# Power.net
KiCad netlist of a schematic drawn in Altium Designer
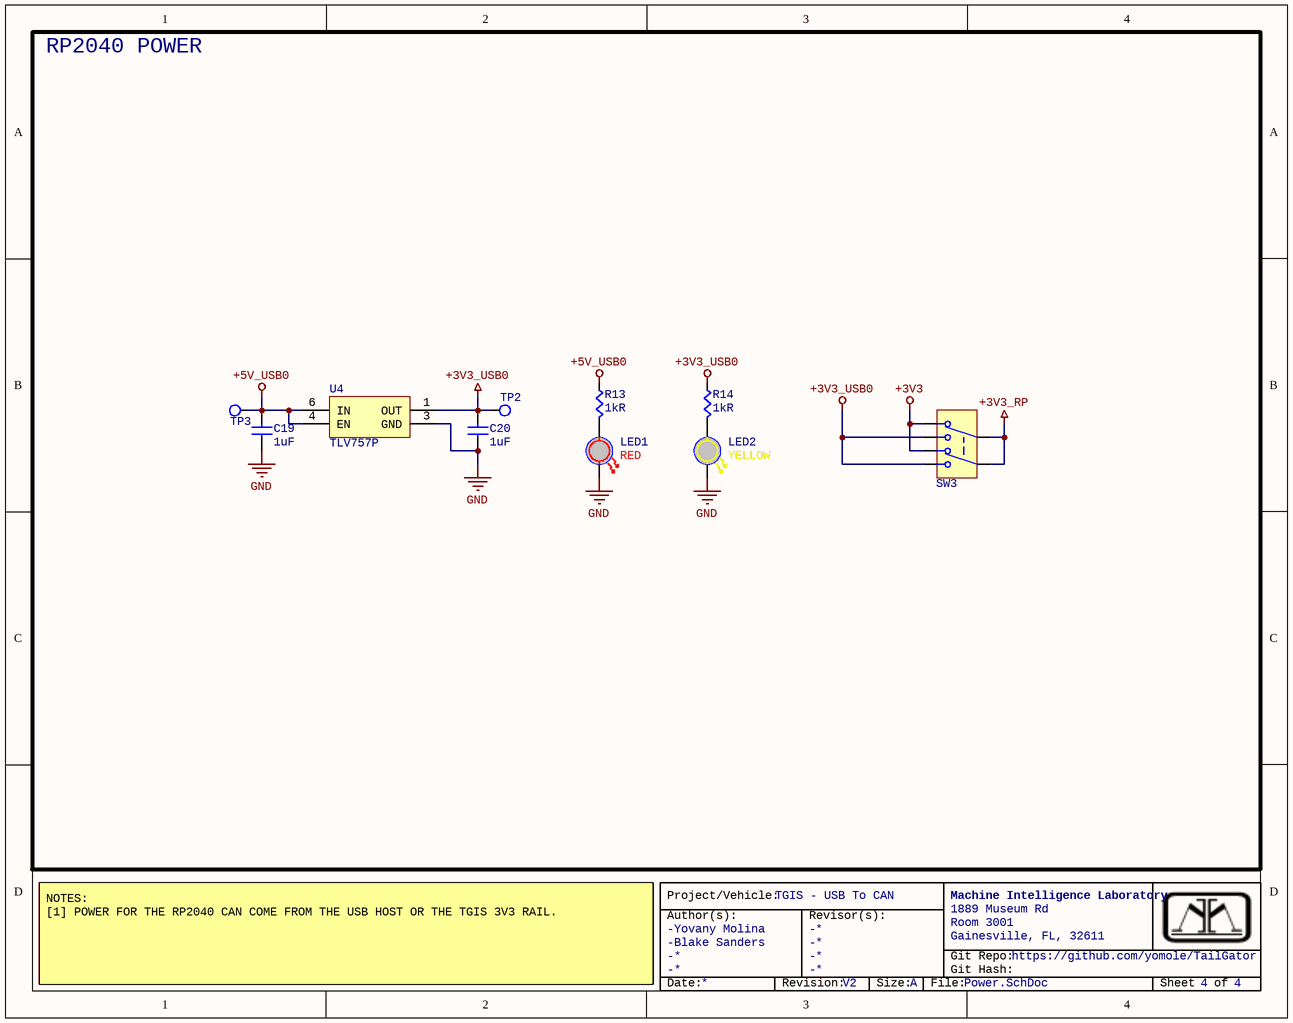
[diagram p0: Power.SchDoc]

(export (version "E")
  (design (tool "Eeschema 10.0.6"))
  (components
    (comp (ref "C19")
      (value "1uF")
      (footprint "CAPC0603")
      (description "Ceramic Capacitor, Multilayer, Cera")
      (fields (field (name "PART NUMBER") "CC0603KRX7R7BB105") (field (name "MANUFACTURER") "Yageo"))
      (libsource (lib "Parts") (part "NP_Capacitor"))
    )
    (comp (ref "C20")
      (value "1uF")
      (footprint "CAPC0603")
      (description "Ceramic Capacitor, Multilayer, Cera")
      (fields (field (name "PART NUMBER") "CC0603KRX7R7BB105") (field (name "MANUFACTURER") "Yageo"))
      (libsource (lib "Parts") (part "NP_Capacitor"))
    )
    (comp (ref "LED1")
      (value "RED")
      (footprint "LED0603")
      (description "Single Color LED, Red, Water Clear,")
      (fields (field (name "PART NUMBER") "150060RS75000") (field (name "MANUFACTURER") "Wurth Electronics"))
      (libsource (lib "Parts") (part "LED_Red"))
    )
    (comp (ref "LED2")
      (value "YELLOW")
      (footprint "LED0603")
      (description "Single Color LED, Yellow, Water Cle")
      (fields (field (name "PART NUMBER") "150060YS75000") (field (name "MANUFACTURER") "Wurth Electronics"))
      (libsource (lib "Parts") (part "LED_Yellow"))
    )
    (comp (ref "R13")
      (value "1kR")
      (footprint "RES0603")
      (description "Fixed Resistor, Metal Glaze/thick F")
      (fields (field (name "PART NUMBER") "RC0603FR-071KL") (field (name "POWER") "100mW"))
      (libsource (lib "Parts") (part "Resistor"))
    )
    (comp (ref "R14")
      (value "1kR")
      (footprint "RES0603")
      (description "Fixed Resistor, Metal Glaze/thick F")
      (fields (field (name "PART NUMBER") "RC0603FR-071KL") (field (name "POWER") "100mW"))
      (libsource (lib "Parts") (part "Resistor"))
    )
    (comp (ref "SW3")
      (value "JS202011SCQN")
      (footprint "SW_JS202011SCQN")
      (description "Slide Switch DPDT Surface Mount")
      (libsource (lib "TGIS_Power") (part "JS202011SCQN"))
    )
    (comp (ref "TP2") (value "TP") (footprint "TPAD-60MIL") (libsource (lib "TGIS") (part "TP")))
    (comp (ref "TP3") (value "TP") (footprint "TPAD-60MIL") (libsource (lib "TGIS") (part "TP")))
    (comp (ref "U4")
      (value "TLV757P")
      (footprint "VREG_TLV75733PDRVR")
      (description "Linear Voltage Regulator IC Positive Fixed 1 Output 1A 6-WSON (2x2)")
      (libsource (lib "TGIS_Power") (part "TLV75733PDRVR"))
    )
  )
  (nets
    (net (code "1") (name "+3V3") (class "Default")
      (node (ref "SW3") (pin "1") (pinfunction "1_1") (pintype "passive"))
      (node (ref "SW3") (pin "4") (pinfunction "4_4") (pintype "passive"))
    )
    (net (code "2") (name "+3V3_RP") (class "Default")
      (node (ref "SW3") (pin "2") (pinfunction "2_2") (pintype "passive"))
      (node (ref "SW3") (pin "5") (pinfunction "5_5") (pintype "passive"))
    )
    (net (code "3") (name "+3V3_USB0") (class "Default")
      (node (ref "C20") (pin "2") (pinfunction "B_2") (pintype "passive"))
      (node (ref "R14") (pin "2") (pinfunction "B_2") (pintype "passive"))
      (node (ref "SW3") (pin "3") (pinfunction "3_3") (pintype "passive"))
      (node (ref "SW3") (pin "6") (pinfunction "6_6") (pintype "passive"))
      (node (ref "TP2") (pin "1") (pinfunction "1_1") (pintype "passive"))
      (node (ref "U4") (pin "1") (pinfunction "OUT_1") (pintype "passive"))
    )
    (net (code "4") (name "+5V_USB0") (class "Default")
      (node (ref "C19") (pin "2") (pinfunction "B_2") (pintype "passive"))
      (node (ref "R13") (pin "2") (pinfunction "B_2") (pintype "passive"))
      (node (ref "TP3") (pin "1") (pinfunction "1_1") (pintype "passive"))
      (node (ref "U4") (pin "4") (pinfunction "EN_4") (pintype "passive"))
      (node (ref "U4") (pin "6") (pinfunction "IN_6") (pintype "passive"))
    )
    (net (code "5") (name "GND") (class "Default")
      (node (ref "C19") (pin "1") (pinfunction "A_1") (pintype "passive"))
      (node (ref "C20") (pin "1") (pinfunction "A_1") (pintype "passive"))
      (node (ref "LED1") (pin "C") (pinfunction "C_C") (pintype "passive"))
      (node (ref "LED2") (pin "C") (pinfunction "C_C") (pintype "passive"))
      (node (ref "U4") (pin "3") (pinfunction "GND_3") (pintype "passive"))
    )
    (net (code "6") (name "Net-(R13-A)") (class "Default")
      (node (ref "LED1") (pin "A") (pinfunction "A_A") (pintype "passive"))
      (node (ref "R13") (pin "1") (pinfunction "A_1") (pintype "passive"))
    )
    (net (code "7") (name "Net-(R14-A)") (class "Default")
      (node (ref "LED2") (pin "A") (pinfunction "A_A") (pintype "passive"))
      (node (ref "R14") (pin "1") (pinfunction "A_1") (pintype "passive"))
    )
  )
)
